# DisplayModulev3.net
KiCad netlist of a schematic drawn in EAGLE
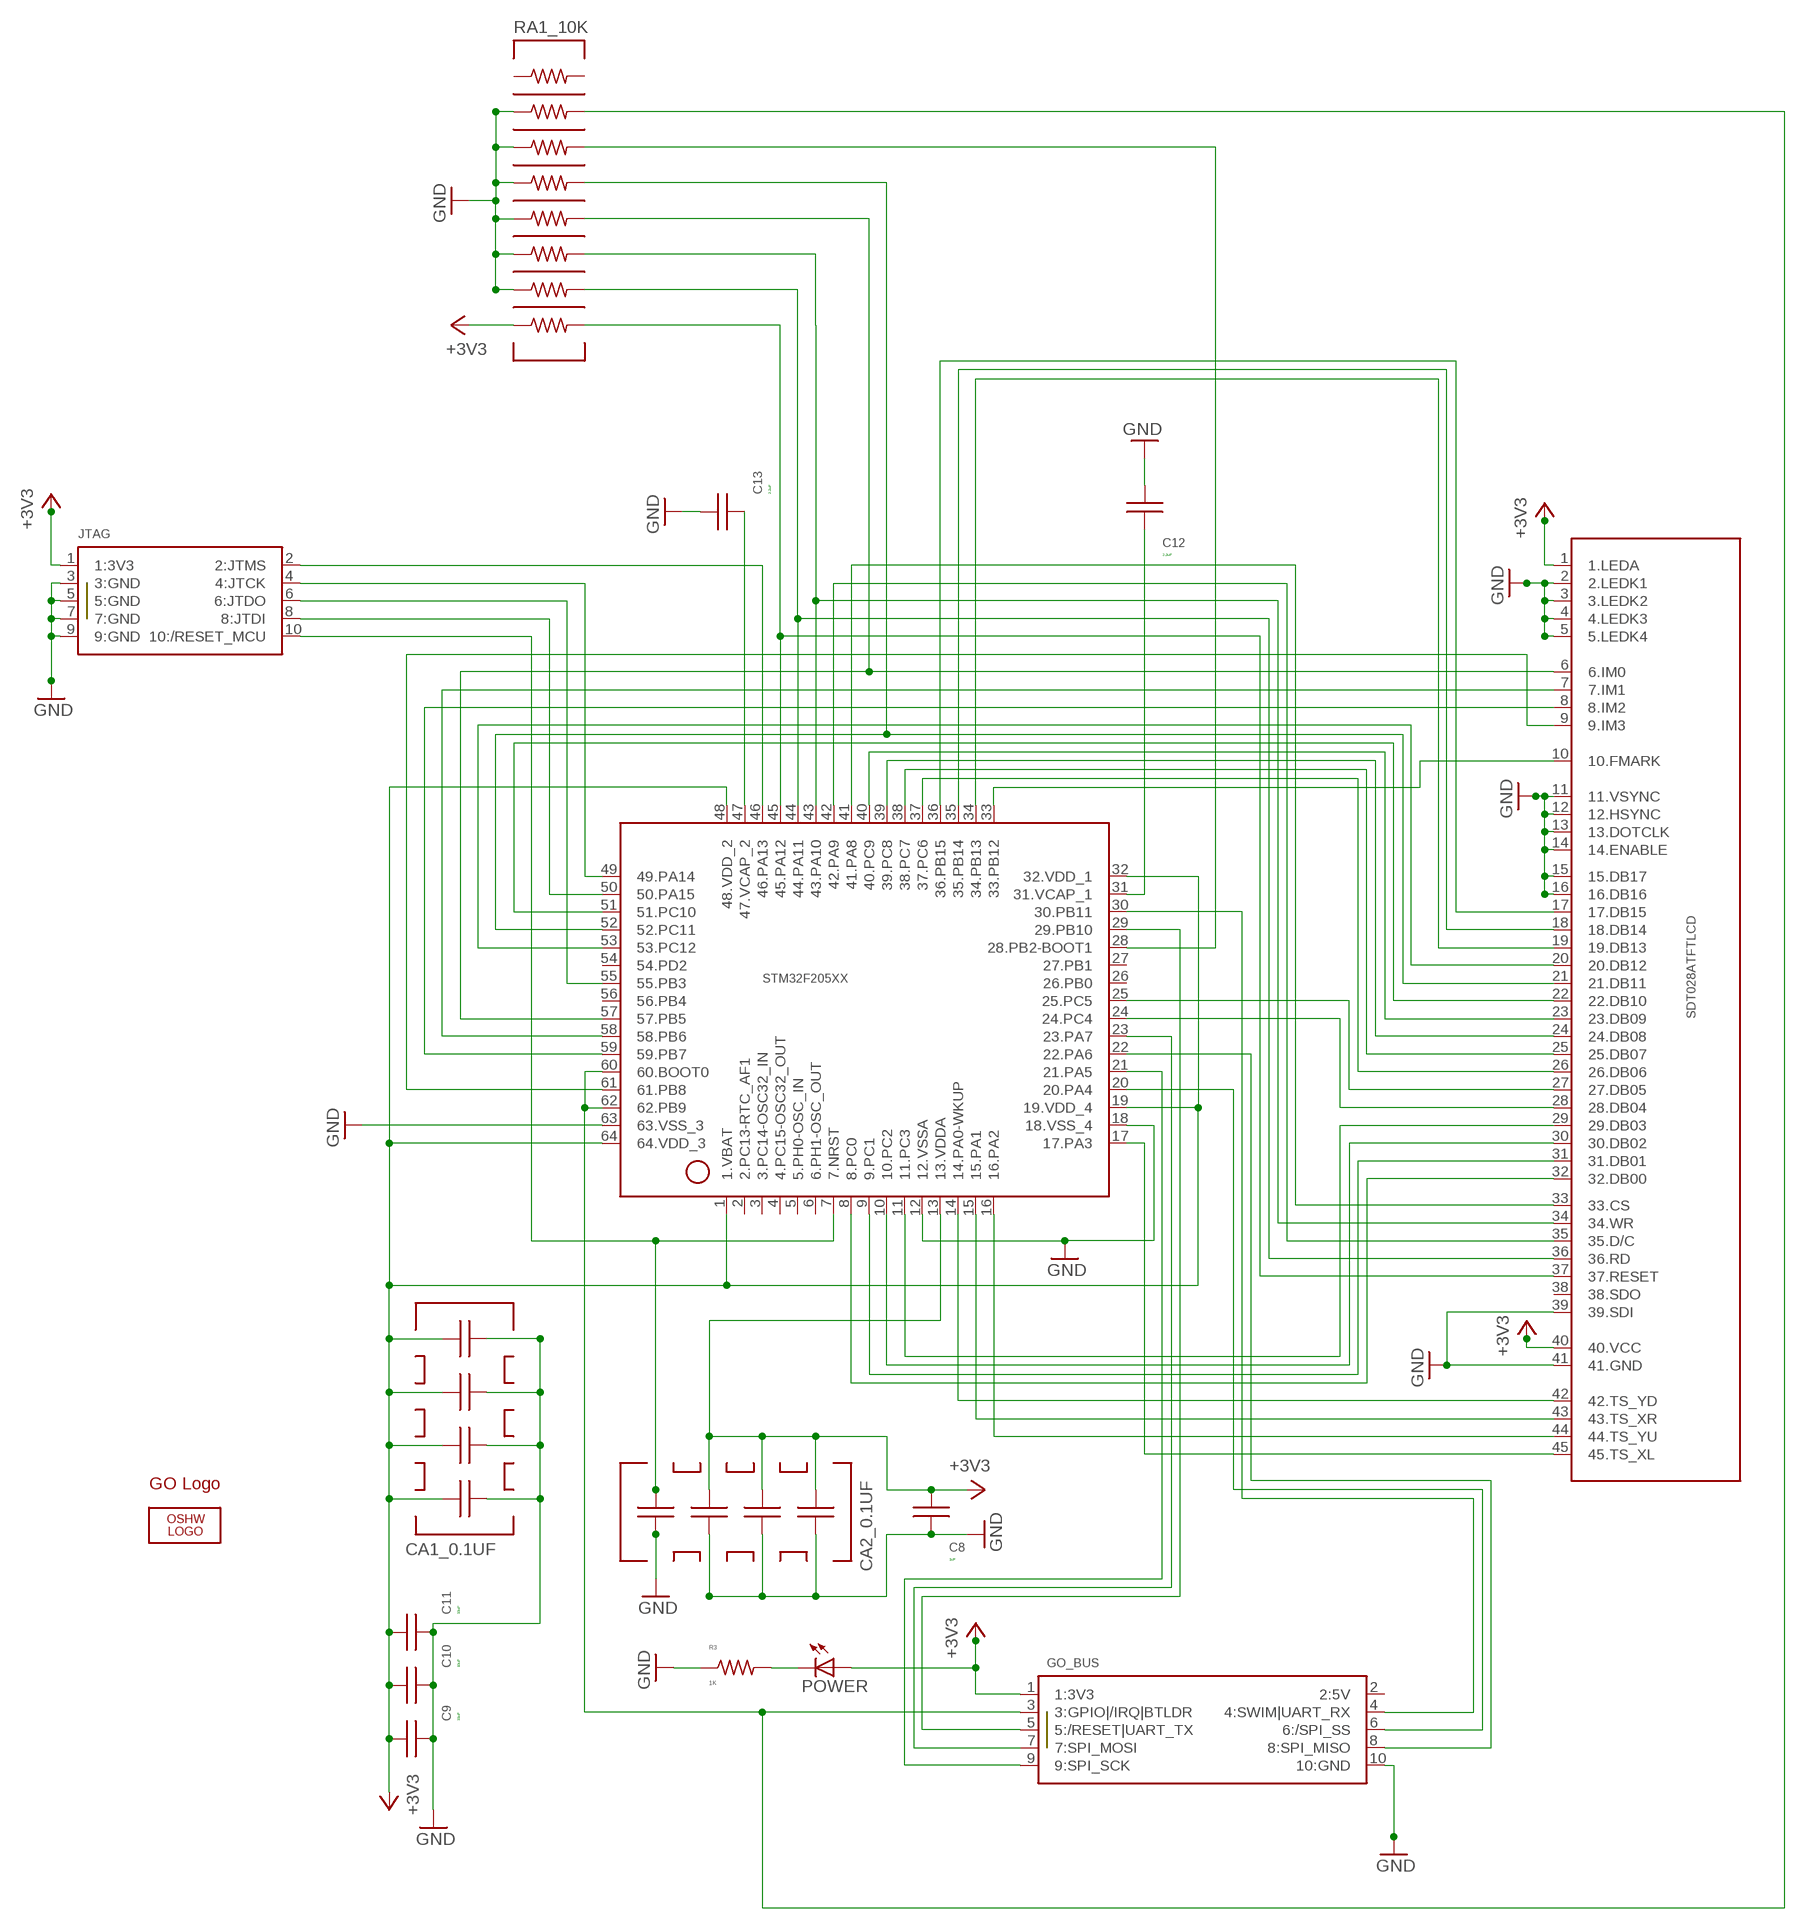
[diagram p0: schematic, sheet 1]

(export (version "E")
  (design (tool "Eeschema 10.0.6"))
  (components
    (comp (ref "C8")
      (value "1UF")
      (footprint "eagle-import:0805")
      (libsource (lib "eagle-import") (part "MURATA_GRM_1UF_CER_CAP_0805"))
    )
    (comp (ref "C9")
      (value "10UF")
      (footprint "eagle-import:0805")
      (libsource (lib "eagle-import") (part "MURATA_GRM_10UF_CER_0805"))
    )
    (comp (ref "C10")
      (value "10UF")
      (footprint "eagle-import:0805")
      (libsource (lib "eagle-import") (part "MURATA_GRM_10UF_CER_0805"))
    )
    (comp (ref "C11")
      (value "10UF")
      (footprint "eagle-import:0805")
      (libsource (lib "eagle-import") (part "MURATA_GRM_10UF_CER_0805"))
    )
    (comp (ref "C12")
      (value "2.2UF")
      (footprint "eagle-import:0805")
      (libsource (lib "eagle-import") (part "CAP_CER_2.2UF_0805"))
    )
    (comp (ref "C13")
      (value "2.2UF")
      (footprint "eagle-import:0805")
      (libsource (lib "eagle-import") (part "CAP_CER_2.2UF_0805"))
    )
    (comp (ref "CA1_0.1UF")
      (value "TAYIO-YUDEN_0.1UF_CAP_ARRAY_0805")
      (footprint "eagle-import:TAYIO-YUDEN_CAP_ARRAY_4_CIRCUITS_0805")
      (libsource (lib "eagle-import") (part "TAYIO-YUDEN_0.1UF_CAP_ARRAY_0805"))
    )
    (comp (ref "CA2_0.1UF")
      (value "TAYIO-YUDEN_0.1UF_CAP_ARRAY_0805")
      (footprint "eagle-import:TAYIO-YUDEN_CAP_ARRAY_4_CIRCUITS_0805")
      (libsource (lib "eagle-import") (part "TAYIO-YUDEN_0.1UF_CAP_ARRAY_0805"))
    )
    (comp (ref "GO_BUS")
      (value "GO_CONNECTOR")
      (footprint "eagle-import:FCI-1.27X1.27MM_10PIN_HEADER_SHROUDED_SMT")
      (libsource (lib "eagle-import") (part "GO_CONNECTOR"))
    )
    (comp (ref "JTAG")
      (value "FCI-MINI_JTAG_HEADER")
      (footprint "eagle-import:FCI-MINI_JTAG_CONNECTOR")
      (libsource (lib "eagle-import") (part "FCI-MINI_JTAG_HEADER"))
    )
    (comp (ref "LOGO1")
      (value "OSHW_LOGO_FILLX0150-NT")
      (footprint "eagle-import:OSHW_FILLX150_NOTEXT")
      (libsource (lib "eagle-import") (part "OSHW_LOGO_FILLX0150-NT"))
    )
    (comp (ref "POWER")
      (value "LITEON_WHITE_LED_0805")
      (footprint "eagle-import:0805")
      (libsource (lib "eagle-import") (part "LITEON_WHITE_LED_0805"))
    )
    (comp (ref "R3")
      (value "1K")
      (footprint "eagle-import:0805")
      (libsource (lib "eagle-import") (part "RESISTOR_0805"))
    )
    (comp (ref "RA1_10K")
      (value "10K")
      (footprint "eagle-import:CTS_742C163_RES_ARRAY_8_CIRCUITS_0603")
      (libsource (lib "eagle-import") (part "CTS_742C163_RES_ARRAY_8_CIRCUITS_0603"))
    )
    (comp (ref "SDT028ATFTLCD")
      (value "HIROSE-FH12")
      (footprint "eagle-import:HIROSE-FH12S-45S-0.5SH")
      (libsource (lib "eagle-import") (part "HIROSE-FH12"))
    )
    (comp (ref "STM32F205XX")
      (value "STM32F205XXCORTEXM3RET")
      (footprint "eagle-import:STM32F205XX_LQFP64")
      (libsource (lib "eagle-import") (part "STM32F205XXRETCORTEXM3"))
    )
    (comp (ref "U$1")
      (value "GO_LOGO")
      (footprint "eagle-import:GO_LOGO")
      (libsource (lib "eagle-import") (part "GO_LOGO"))
    )
  )
  (nets
    (net (code "1") (name "+3V3") (class "Default")
      (node (ref "C10") (pin "K") (pinfunction "2_K") (pintype "passive"))
      (node (ref "C11") (pin "K") (pinfunction "2_K") (pintype "passive"))
      (node (ref "C8") (pin "K") (pinfunction "2_K") (pintype "passive"))
      (node (ref "C9") (pin "K") (pinfunction "2_K") (pintype "passive"))
      (node (ref "CA1_0.1UF") (pin "2") (pinfunction "2_2") (pintype "passive"))
      (node (ref "CA1_0.1UF") (pin "4") (pinfunction "4_4") (pintype "passive"))
      (node (ref "CA1_0.1UF") (pin "6") (pinfunction "6_6") (pintype "passive"))
      (node (ref "CA1_0.1UF") (pin "8") (pinfunction "8_8") (pintype "passive"))
      (node (ref "CA2_0.1UF") (pin "1") (pinfunction "1_1") (pintype "passive"))
      (node (ref "CA2_0.1UF") (pin "3") (pinfunction "3_3") (pintype "passive"))
      (node (ref "CA2_0.1UF") (pin "7") (pinfunction "7_7") (pintype "passive"))
      (node (ref "GO_BUS") (pin "1") (pinfunction "1:3V3_1") (pintype "power_in"))
      (node (ref "JTAG") (pin "1") (pinfunction "1:3V3_1") (pintype "power_in"))
      (node (ref "POWER") (pin "A") (pinfunction "A_A") (pintype "passive"))
      (node (ref "RA1_10K") (pin "16") (pinfunction "16_16") (pintype "passive"))
      (node (ref "SDT028ATFTLCD") (pin "1") (pinfunction "1.LEDA_1") (pintype "power_in"))
      (node (ref "SDT028ATFTLCD") (pin "40") (pinfunction "40.VCC_40") (pintype "power_in"))
      (node (ref "STM32F205XX") (pin "1") (pinfunction "1.VBAT_1") (pintype "power_in"))
      (node (ref "STM32F205XX") (pin "13") (pinfunction "13.VDDA_13") (pintype "power_in"))
      (node (ref "STM32F205XX") (pin "19") (pinfunction "19.VDD_4_19") (pintype "power_in"))
      (node (ref "STM32F205XX") (pin "32") (pinfunction "32.VDD_1_32") (pintype "power_in"))
      (node (ref "STM32F205XX") (pin "48") (pinfunction "48.VDD_2_48") (pintype "power_in"))
      (node (ref "STM32F205XX") (pin "64") (pinfunction "64.VDD_3_64") (pintype "power_in"))
    )
    (net (code "2") (name "/2:5V") (class "Default")
      (node (ref "GO_BUS") (pin "2") (pinfunction "2:5V_2") (pintype "power_in"))
    )
    (net (code "3") (name "GND") (class "Default")
      (node (ref "C10") (pin "A") (pinfunction "1_A") (pintype "passive"))
      (node (ref "C11") (pin "A") (pinfunction "1_A") (pintype "passive"))
      (node (ref "C12") (pin "K") (pinfunction "2_K") (pintype "passive"))
      (node (ref "C13") (pin "K") (pinfunction "2_K") (pintype "passive"))
      (node (ref "C8") (pin "A") (pinfunction "1_A") (pintype "passive"))
      (node (ref "C9") (pin "A") (pinfunction "1_A") (pintype "passive"))
      (node (ref "CA1_0.1UF") (pin "1") (pinfunction "1_1") (pintype "passive"))
      (node (ref "CA1_0.1UF") (pin "3") (pinfunction "3_3") (pintype "passive"))
      (node (ref "CA1_0.1UF") (pin "5") (pinfunction "5_5") (pintype "passive"))
      (node (ref "CA1_0.1UF") (pin "7") (pinfunction "7_7") (pintype "passive"))
      (node (ref "CA2_0.1UF") (pin "2") (pinfunction "2_2") (pintype "passive"))
      (node (ref "CA2_0.1UF") (pin "4") (pinfunction "4_4") (pintype "passive"))
      (node (ref "CA2_0.1UF") (pin "6") (pinfunction "6_6") (pintype "passive"))
      (node (ref "CA2_0.1UF") (pin "8") (pinfunction "8_8") (pintype "passive"))
      (node (ref "GO_BUS") (pin "10") (pinfunction "10:GND_10") (pintype "passive"))
      (node (ref "JTAG") (pin "3") (pinfunction "3:GND_3") (pintype "passive"))
      (node (ref "JTAG") (pin "5") (pinfunction "5:GND_5") (pintype "passive"))
      (node (ref "JTAG") (pin "7") (pinfunction "7:GND_7") (pintype "passive"))
      (node (ref "JTAG") (pin "9") (pinfunction "9:GND_9") (pintype "passive"))
      (node (ref "R3") (pin "A") (pinfunction "1_A") (pintype "passive"))
      (node (ref "RA1_10K") (pin "10") (pinfunction "10_10") (pintype "passive"))
      (node (ref "RA1_10K") (pin "12") (pinfunction "12_12") (pintype "passive"))
      (node (ref "RA1_10K") (pin "14") (pinfunction "14_14") (pintype "passive"))
      (node (ref "RA1_10K") (pin "4") (pinfunction "4_4") (pintype "passive"))
      (node (ref "RA1_10K") (pin "6") (pinfunction "6_6") (pintype "passive"))
      (node (ref "RA1_10K") (pin "8") (pinfunction "8_8") (pintype "passive"))
      (node (ref "SDT028ATFTLCD") (pin "11") (pinfunction "11.VSYNC_11") (pintype "input"))
      (node (ref "SDT028ATFTLCD") (pin "12") (pinfunction "12.HSYNC_12") (pintype "input"))
      (node (ref "SDT028ATFTLCD") (pin "13") (pinfunction "13.DOTCLK_13") (pintype "input"))
      (node (ref "SDT028ATFTLCD") (pin "14") (pinfunction "14.ENABLE_14") (pintype "input"))
      (node (ref "SDT028ATFTLCD") (pin "15") (pinfunction "15.DB17_15") (pintype "bidirectional"))
      (node (ref "SDT028ATFTLCD") (pin "16") (pinfunction "16.DB16_16") (pintype "bidirectional"))
      (node (ref "SDT028ATFTLCD") (pin "2") (pinfunction "2.LEDK1_2") (pintype "passive"))
      (node (ref "SDT028ATFTLCD") (pin "3") (pinfunction "3.LEDK2_3") (pintype "passive"))
      (node (ref "SDT028ATFTLCD") (pin "39") (pinfunction "39.SDI_39") (pintype "input"))
      (node (ref "SDT028ATFTLCD") (pin "4") (pinfunction "4.LEDK3_4") (pintype "passive"))
      (node (ref "SDT028ATFTLCD") (pin "41") (pinfunction "41.GND_41") (pintype "passive"))
      (node (ref "SDT028ATFTLCD") (pin "5") (pinfunction "5.LEDK4_5") (pintype "passive"))
      (node (ref "STM32F205XX") (pin "12") (pinfunction "12.VSSA_12") (pintype "passive"))
      (node (ref "STM32F205XX") (pin "18") (pinfunction "18.VSS_4_18") (pintype "passive"))
      (node (ref "STM32F205XX") (pin "63") (pinfunction "63.VSS_3_63") (pintype "passive"))
    )
    (net (code "4") (name "Net-(C12-1)") (class "Default")
      (node (ref "C12") (pin "A") (pinfunction "1_A") (pintype "passive"))
      (node (ref "STM32F205XX") (pin "31") (pinfunction "31.VCAP_1_31") (pintype "passive"))
    )
    (net (code "5") (name "Net-(C13-1)") (class "Default")
      (node (ref "C13") (pin "A") (pinfunction "1_A") (pintype "passive"))
      (node (ref "STM32F205XX") (pin "47") (pinfunction "47.VCAP_2_47") (pintype "passive"))
    )
    (net (code "6") (name "Net-(GO_BUS-3:GPIO|{slash}IRQ|BTLDR)") (class "Default")
      (node (ref "GO_BUS") (pin "3") (pinfunction "3:GPIO|/IRQ|BTLDR_3") (pintype "bidirectional"))
      (node (ref "RA1_10K") (pin "3") (pinfunction "3_3") (pintype "passive"))
      (node (ref "STM32F205XX") (pin "60") (pinfunction "60.BOOT0_60") (pintype "bidirectional"))
      (node (ref "STM32F205XX") (pin "62") (pinfunction "62.PB9_62") (pintype "bidirectional"))
    )
    (net (code "7") (name "Net-(GO_BUS-4:SWIM|UART_RX)") (class "Default")
      (node (ref "GO_BUS") (pin "4") (pinfunction "4:SWIM|UART_RX_4") (pintype "bidirectional"))
      (node (ref "STM32F205XX") (pin "30") (pinfunction "30.PB11_30") (pintype "bidirectional"))
    )
    (net (code "8") (name "Net-(GO_BUS-5:{slash}RESET|UART_TX)") (class "Default")
      (node (ref "GO_BUS") (pin "5") (pinfunction "5:/RESET|UART_TX_5") (pintype "bidirectional"))
      (node (ref "STM32F205XX") (pin "29") (pinfunction "29.PB10_29") (pintype "bidirectional"))
    )
    (net (code "9") (name "Net-(GO_BUS-6:{slash}SPI_SS)") (class "Default")
      (node (ref "GO_BUS") (pin "6") (pinfunction "6:/SPI_SS_6") (pintype "bidirectional"))
      (node (ref "STM32F205XX") (pin "20") (pinfunction "20.PA4_20") (pintype "bidirectional"))
    )
    (net (code "10") (name "Net-(GO_BUS-7:SPI_MOSI)") (class "Default")
      (node (ref "GO_BUS") (pin "7") (pinfunction "7:SPI_MOSI_7") (pintype "bidirectional"))
      (node (ref "STM32F205XX") (pin "23") (pinfunction "23.PA7_23") (pintype "bidirectional"))
    )
    (net (code "11") (name "Net-(GO_BUS-8:SPI_MISO)") (class "Default")
      (node (ref "GO_BUS") (pin "8") (pinfunction "8:SPI_MISO_8") (pintype "bidirectional"))
      (node (ref "STM32F205XX") (pin "22") (pinfunction "22.PA6_22") (pintype "bidirectional"))
    )
    (net (code "12") (name "Net-(GO_BUS-9:SPI_SCK)") (class "Default")
      (node (ref "GO_BUS") (pin "9") (pinfunction "9:SPI_SCK_9") (pintype "bidirectional"))
      (node (ref "STM32F205XX") (pin "21") (pinfunction "21.PA5_21") (pintype "bidirectional"))
    )
    (net (code "13") (name "Net-(JTAG-2:JTMS)") (class "Default")
      (node (ref "JTAG") (pin "2") (pinfunction "2:JTMS_2") (pintype "bidirectional"))
      (node (ref "STM32F205XX") (pin "46") (pinfunction "46.PA13_46") (pintype "bidirectional"))
    )
    (net (code "14") (name "Net-(JTAG-4:JTCK)") (class "Default")
      (node (ref "JTAG") (pin "4") (pinfunction "4:JTCK_4") (pintype "bidirectional"))
      (node (ref "STM32F205XX") (pin "49") (pinfunction "49.PA14_49") (pintype "bidirectional"))
    )
    (net (code "15") (name "Net-(JTAG-6:JTDO)") (class "Default")
      (node (ref "JTAG") (pin "6") (pinfunction "6:JTDO_6") (pintype "bidirectional"))
      (node (ref "STM32F205XX") (pin "55") (pinfunction "55.PB3_55") (pintype "bidirectional"))
    )
    (net (code "16") (name "Net-(JTAG-8:JTDI)") (class "Default")
      (node (ref "JTAG") (pin "8") (pinfunction "8:JTDI_8") (pintype "bidirectional"))
      (node (ref "STM32F205XX") (pin "50") (pinfunction "50.PA15_50") (pintype "bidirectional"))
    )
    (net (code "17") (name "Net-(JTAG-10:{slash}RESET_MCU)") (class "Default")
      (node (ref "CA2_0.1UF") (pin "5") (pinfunction "5_5") (pintype "passive"))
      (node (ref "JTAG") (pin "10") (pinfunction "10:/RESET_MCU_10") (pintype "bidirectional"))
      (node (ref "STM32F205XX") (pin "7") (pinfunction "7.NRST_7") (pintype "bidirectional"))
    )
    (net (code "18") (name "Net-(POWER-C)") (class "Default")
      (node (ref "POWER") (pin "K") (pinfunction "C_K") (pintype "passive"))
      (node (ref "R3") (pin "K") (pinfunction "2_K") (pintype "passive"))
    )
    (net (code "19") (name "Net-(SDT028ATFTLCD-6.IM0)") (class "Default")
      (node (ref "RA1_10K") (pin "9") (pinfunction "9_9") (pintype "passive"))
      (node (ref "SDT028ATFTLCD") (pin "6") (pinfunction "6.IM0_6") (pintype "input"))
      (node (ref "STM32F205XX") (pin "57") (pinfunction "57.PB5_57") (pintype "bidirectional"))
    )
    (net (code "20") (name "Net-(SDT028ATFTLCD-7.IM1)") (class "Default")
      (node (ref "SDT028ATFTLCD") (pin "7") (pinfunction "7.IM1_7") (pintype "input"))
      (node (ref "STM32F205XX") (pin "58") (pinfunction "58.PB6_58") (pintype "bidirectional"))
    )
    (net (code "21") (name "Net-(SDT028ATFTLCD-8.IM2)") (class "Default")
      (node (ref "SDT028ATFTLCD") (pin "8") (pinfunction "8.IM2_8") (pintype "input"))
      (node (ref "STM32F205XX") (pin "59") (pinfunction "59.PB7_59") (pintype "bidirectional"))
    )
    (net (code "22") (name "Net-(SDT028ATFTLCD-9.IM3)") (class "Default")
      (node (ref "SDT028ATFTLCD") (pin "9") (pinfunction "9.IM3_9") (pintype "input"))
      (node (ref "STM32F205XX") (pin "61") (pinfunction "61.PB8_61") (pintype "bidirectional"))
    )
    (net (code "23") (name "Net-(SDT028ATFTLCD-10.FMARK)") (class "Default")
      (node (ref "SDT028ATFTLCD") (pin "10") (pinfunction "10.FMARK_10") (pintype "output"))
      (node (ref "STM32F205XX") (pin "33") (pinfunction "33.PB12_33") (pintype "bidirectional"))
    )
    (net (code "24") (name "Net-(SDT028ATFTLCD-17.DB15)") (class "Default")
      (node (ref "SDT028ATFTLCD") (pin "17") (pinfunction "17.DB15_17") (pintype "bidirectional"))
      (node (ref "STM32F205XX") (pin "36") (pinfunction "36.PB15_36") (pintype "bidirectional"))
    )
    (net (code "25") (name "Net-(SDT028ATFTLCD-18.DB14)") (class "Default")
      (node (ref "SDT028ATFTLCD") (pin "18") (pinfunction "18.DB14_18") (pintype "bidirectional"))
      (node (ref "STM32F205XX") (pin "35") (pinfunction "35.PB14_35") (pintype "bidirectional"))
    )
    (net (code "26") (name "Net-(SDT028ATFTLCD-19.DB13)") (class "Default")
      (node (ref "SDT028ATFTLCD") (pin "19") (pinfunction "19.DB13_19") (pintype "bidirectional"))
      (node (ref "STM32F205XX") (pin "34") (pinfunction "34.PB13_34") (pintype "bidirectional"))
    )
    (net (code "27") (name "Net-(SDT028ATFTLCD-20.DB12)") (class "Default")
      (node (ref "SDT028ATFTLCD") (pin "20") (pinfunction "20.DB12_20") (pintype "bidirectional"))
      (node (ref "STM32F205XX") (pin "53") (pinfunction "53.PC12_53") (pintype "bidirectional"))
    )
    (net (code "28") (name "Net-(SDT028ATFTLCD-21.DB11)") (class "Default")
      (node (ref "RA1_10K") (pin "7") (pinfunction "7_7") (pintype "passive"))
      (node (ref "SDT028ATFTLCD") (pin "21") (pinfunction "21.DB11_21") (pintype "bidirectional"))
      (node (ref "STM32F205XX") (pin "52") (pinfunction "52.PC11_52") (pintype "bidirectional"))
    )
    (net (code "29") (name "Net-(SDT028ATFTLCD-22.DB10)") (class "Default")
      (node (ref "SDT028ATFTLCD") (pin "22") (pinfunction "22.DB10_22") (pintype "bidirectional"))
      (node (ref "STM32F205XX") (pin "51") (pinfunction "51.PC10_51") (pintype "bidirectional"))
    )
    (net (code "30") (name "Net-(SDT028ATFTLCD-23.DB09)") (class "Default")
      (node (ref "SDT028ATFTLCD") (pin "23") (pinfunction "23.DB09_23") (pintype "bidirectional"))
      (node (ref "STM32F205XX") (pin "40") (pinfunction "40.PC9_40") (pintype "bidirectional"))
    )
    (net (code "31") (name "Net-(SDT028ATFTLCD-24.DB08)") (class "Default")
      (node (ref "SDT028ATFTLCD") (pin "24") (pinfunction "24.DB08_24") (pintype "bidirectional"))
      (node (ref "STM32F205XX") (pin "39") (pinfunction "39.PC8_39") (pintype "bidirectional"))
    )
    (net (code "32") (name "Net-(SDT028ATFTLCD-25.DB07)") (class "Default")
      (node (ref "SDT028ATFTLCD") (pin "25") (pinfunction "25.DB07_25") (pintype "bidirectional"))
      (node (ref "STM32F205XX") (pin "38") (pinfunction "38.PC7_38") (pintype "bidirectional"))
    )
    (net (code "33") (name "Net-(SDT028ATFTLCD-26.DB06)") (class "Default")
      (node (ref "SDT028ATFTLCD") (pin "26") (pinfunction "26.DB06_26") (pintype "bidirectional"))
      (node (ref "STM32F205XX") (pin "37") (pinfunction "37.PC6_37") (pintype "bidirectional"))
    )
    (net (code "34") (name "Net-(SDT028ATFTLCD-27.DB05)") (class "Default")
      (node (ref "SDT028ATFTLCD") (pin "27") (pinfunction "27.DB05_27") (pintype "bidirectional"))
      (node (ref "STM32F205XX") (pin "25") (pinfunction "25.PC5_25") (pintype "bidirectional"))
    )
    (net (code "35") (name "Net-(SDT028ATFTLCD-28.DB04)") (class "Default")
      (node (ref "SDT028ATFTLCD") (pin "28") (pinfunction "28.DB04_28") (pintype "bidirectional"))
      (node (ref "STM32F205XX") (pin "24") (pinfunction "24.PC4_24") (pintype "bidirectional"))
    )
    (net (code "36") (name "Net-(SDT028ATFTLCD-29.DB03)") (class "Default")
      (node (ref "SDT028ATFTLCD") (pin "29") (pinfunction "29.DB03_29") (pintype "bidirectional"))
      (node (ref "STM32F205XX") (pin "11") (pinfunction "11.PC3_11") (pintype "bidirectional"))
    )
    (net (code "37") (name "Net-(SDT028ATFTLCD-30.DB02)") (class "Default")
      (node (ref "SDT028ATFTLCD") (pin "30") (pinfunction "30.DB02_30") (pintype "bidirectional"))
      (node (ref "STM32F205XX") (pin "10") (pinfunction "10.PC2_10") (pintype "bidirectional"))
    )
    (net (code "38") (name "Net-(SDT028ATFTLCD-31.DB01)") (class "Default")
      (node (ref "SDT028ATFTLCD") (pin "31") (pinfunction "31.DB01_31") (pintype "bidirectional"))
      (node (ref "STM32F205XX") (pin "9") (pinfunction "9.PC1_9") (pintype "bidirectional"))
    )
    (net (code "39") (name "Net-(SDT028ATFTLCD-32.DB00)") (class "Default")
      (node (ref "SDT028ATFTLCD") (pin "32") (pinfunction "32.DB00_32") (pintype "bidirectional"))
      (node (ref "STM32F205XX") (pin "8") (pinfunction "8.PC0_8") (pintype "bidirectional"))
    )
    (net (code "40") (name "Net-(SDT028ATFTLCD-33.CS)") (class "Default")
      (node (ref "SDT028ATFTLCD") (pin "33") (pinfunction "33.CS_33") (pintype "input"))
      (node (ref "STM32F205XX") (pin "41") (pinfunction "41.PA8_41") (pintype "bidirectional"))
    )
    (net (code "41") (name "Net-(SDT028ATFTLCD-34.WR)") (class "Default")
      (node (ref "RA1_10K") (pin "11") (pinfunction "11_11") (pintype "passive"))
      (node (ref "SDT028ATFTLCD") (pin "34") (pinfunction "34.WR_34") (pintype "input"))
      (node (ref "STM32F205XX") (pin "43") (pinfunction "43.PA10_43") (pintype "bidirectional"))
    )
    (net (code "42") (name "Net-(SDT028ATFTLCD-35.D{slash}C)") (class "Default")
      (node (ref "SDT028ATFTLCD") (pin "35") (pinfunction "35.D/C_35") (pintype "input"))
      (node (ref "STM32F205XX") (pin "42") (pinfunction "42.PA9_42") (pintype "bidirectional"))
    )
    (net (code "43") (name "Net-(SDT028ATFTLCD-36.RD)") (class "Default")
      (node (ref "RA1_10K") (pin "13") (pinfunction "13_13") (pintype "passive"))
      (node (ref "SDT028ATFTLCD") (pin "36") (pinfunction "36.RD_36") (pintype "input"))
      (node (ref "STM32F205XX") (pin "44") (pinfunction "44.PA11_44") (pintype "bidirectional"))
    )
    (net (code "44") (name "Net-(SDT028ATFTLCD-37.RESET)") (class "Default")
      (node (ref "RA1_10K") (pin "15") (pinfunction "15_15") (pintype "passive"))
      (node (ref "SDT028ATFTLCD") (pin "37") (pinfunction "37.RESET_37") (pintype "input"))
      (node (ref "STM32F205XX") (pin "45") (pinfunction "45.PA12_45") (pintype "bidirectional"))
    )
    (net (code "45") (name "Net-(SDT028ATFTLCD-42.TS_YD)") (class "Default")
      (node (ref "SDT028ATFTLCD") (pin "42") (pinfunction "42.TS_YD_42") (pintype "bidirectional"))
      (node (ref "STM32F205XX") (pin "14") (pinfunction "14.PA0-WKUP_14") (pintype "bidirectional"))
    )
    (net (code "46") (name "Net-(SDT028ATFTLCD-43.TS_XR)") (class "Default")
      (node (ref "SDT028ATFTLCD") (pin "43") (pinfunction "43.TS_XR_43") (pintype "bidirectional"))
      (node (ref "STM32F205XX") (pin "15") (pinfunction "15.PA1_15") (pintype "bidirectional"))
    )
    (net (code "47") (name "Net-(SDT028ATFTLCD-44.TS_YU)") (class "Default")
      (node (ref "SDT028ATFTLCD") (pin "44") (pinfunction "44.TS_YU_44") (pintype "bidirectional"))
      (node (ref "STM32F205XX") (pin "16") (pinfunction "16.PA2_16") (pintype "bidirectional"))
    )
    (net (code "48") (name "Net-(SDT028ATFTLCD-45.TS_XL)") (class "Default")
      (node (ref "SDT028ATFTLCD") (pin "45") (pinfunction "45.TS_XL_45") (pintype "bidirectional"))
      (node (ref "STM32F205XX") (pin "17") (pinfunction "17.PA3_17") (pintype "bidirectional"))
    )
    (net (code "49") (name "Net-(STM32F205XX-28.PB2-BOOT1)") (class "Default")
      (node (ref "RA1_10K") (pin "5") (pinfunction "5_5") (pintype "passive"))
      (node (ref "STM32F205XX") (pin "28") (pinfunction "28.PB2-BOOT1_28") (pintype "bidirectional"))
    )
    (net (code "50") (name "unconnected-(RA1_10K-Pad1)") (class "Default")
      (node (ref "RA1_10K") (pin "1") (pinfunction "1_1") (pintype "passive"))
    )
    (net (code "51") (name "unconnected-(RA1_10K-Pad2)") (class "Default")
      (node (ref "RA1_10K") (pin "2") (pinfunction "2_2") (pintype "passive"))
    )
    (net (code "52") (name "unconnected-(SDT028ATFTLCD-38.SDO-Pad38)") (class "Default")
      (node (ref "SDT028ATFTLCD") (pin "38") (pinfunction "38.SDO_38") (pintype "output"))
    )
    (net (code "53") (name "unconnected-(STM32F205XX-2.PC13-RTC_AF1-Pad2)") (class "Default")
      (node (ref "STM32F205XX") (pin "2") (pinfunction "2.PC13-RTC_AF1_2") (pintype "bidirectional"))
    )
    (net (code "54") (name "unconnected-(STM32F205XX-3.PC14-OSC32_IN-Pad3)") (class "Default")
      (node (ref "STM32F205XX") (pin "3") (pinfunction "3.PC14-OSC32_IN_3") (pintype "bidirectional"))
    )
    (net (code "55") (name "unconnected-(STM32F205XX-4.PC15-OSC32_OUT-Pad4)") (class "Default")
      (node (ref "STM32F205XX") (pin "4") (pinfunction "4.PC15-OSC32_OUT_4") (pintype "bidirectional"))
    )
    (net (code "56") (name "unconnected-(STM32F205XX-5.PH0-OSC_IN-Pad5)") (class "Default")
      (node (ref "STM32F205XX") (pin "5") (pinfunction "5.PH0-OSC_IN_5") (pintype "bidirectional"))
    )
    (net (code "57") (name "unconnected-(STM32F205XX-6.PH1-OSC_OUT-Pad6)") (class "Default")
      (node (ref "STM32F205XX") (pin "6") (pinfunction "6.PH1-OSC_OUT_6") (pintype "bidirectional"))
    )
    (net (code "58") (name "unconnected-(STM32F205XX-26.PB0-Pad26)") (class "Default")
      (node (ref "STM32F205XX") (pin "26") (pinfunction "26.PB0_26") (pintype "bidirectional"))
    )
    (net (code "59") (name "unconnected-(STM32F205XX-27.PB1-Pad27)") (class "Default")
      (node (ref "STM32F205XX") (pin "27") (pinfunction "27.PB1_27") (pintype "bidirectional"))
    )
    (net (code "60") (name "unconnected-(STM32F205XX-54.PD2-Pad54)") (class "Default")
      (node (ref "STM32F205XX") (pin "54") (pinfunction "54.PD2_54") (pintype "bidirectional"))
    )
    (net (code "61") (name "unconnected-(STM32F205XX-56.PB4-Pad56)") (class "Default")
      (node (ref "STM32F205XX") (pin "56") (pinfunction "56.PB4_56") (pintype "bidirectional"))
    )
  )
)
